# Sound.net
KiCad netlist of a schematic drawn in EAGLE
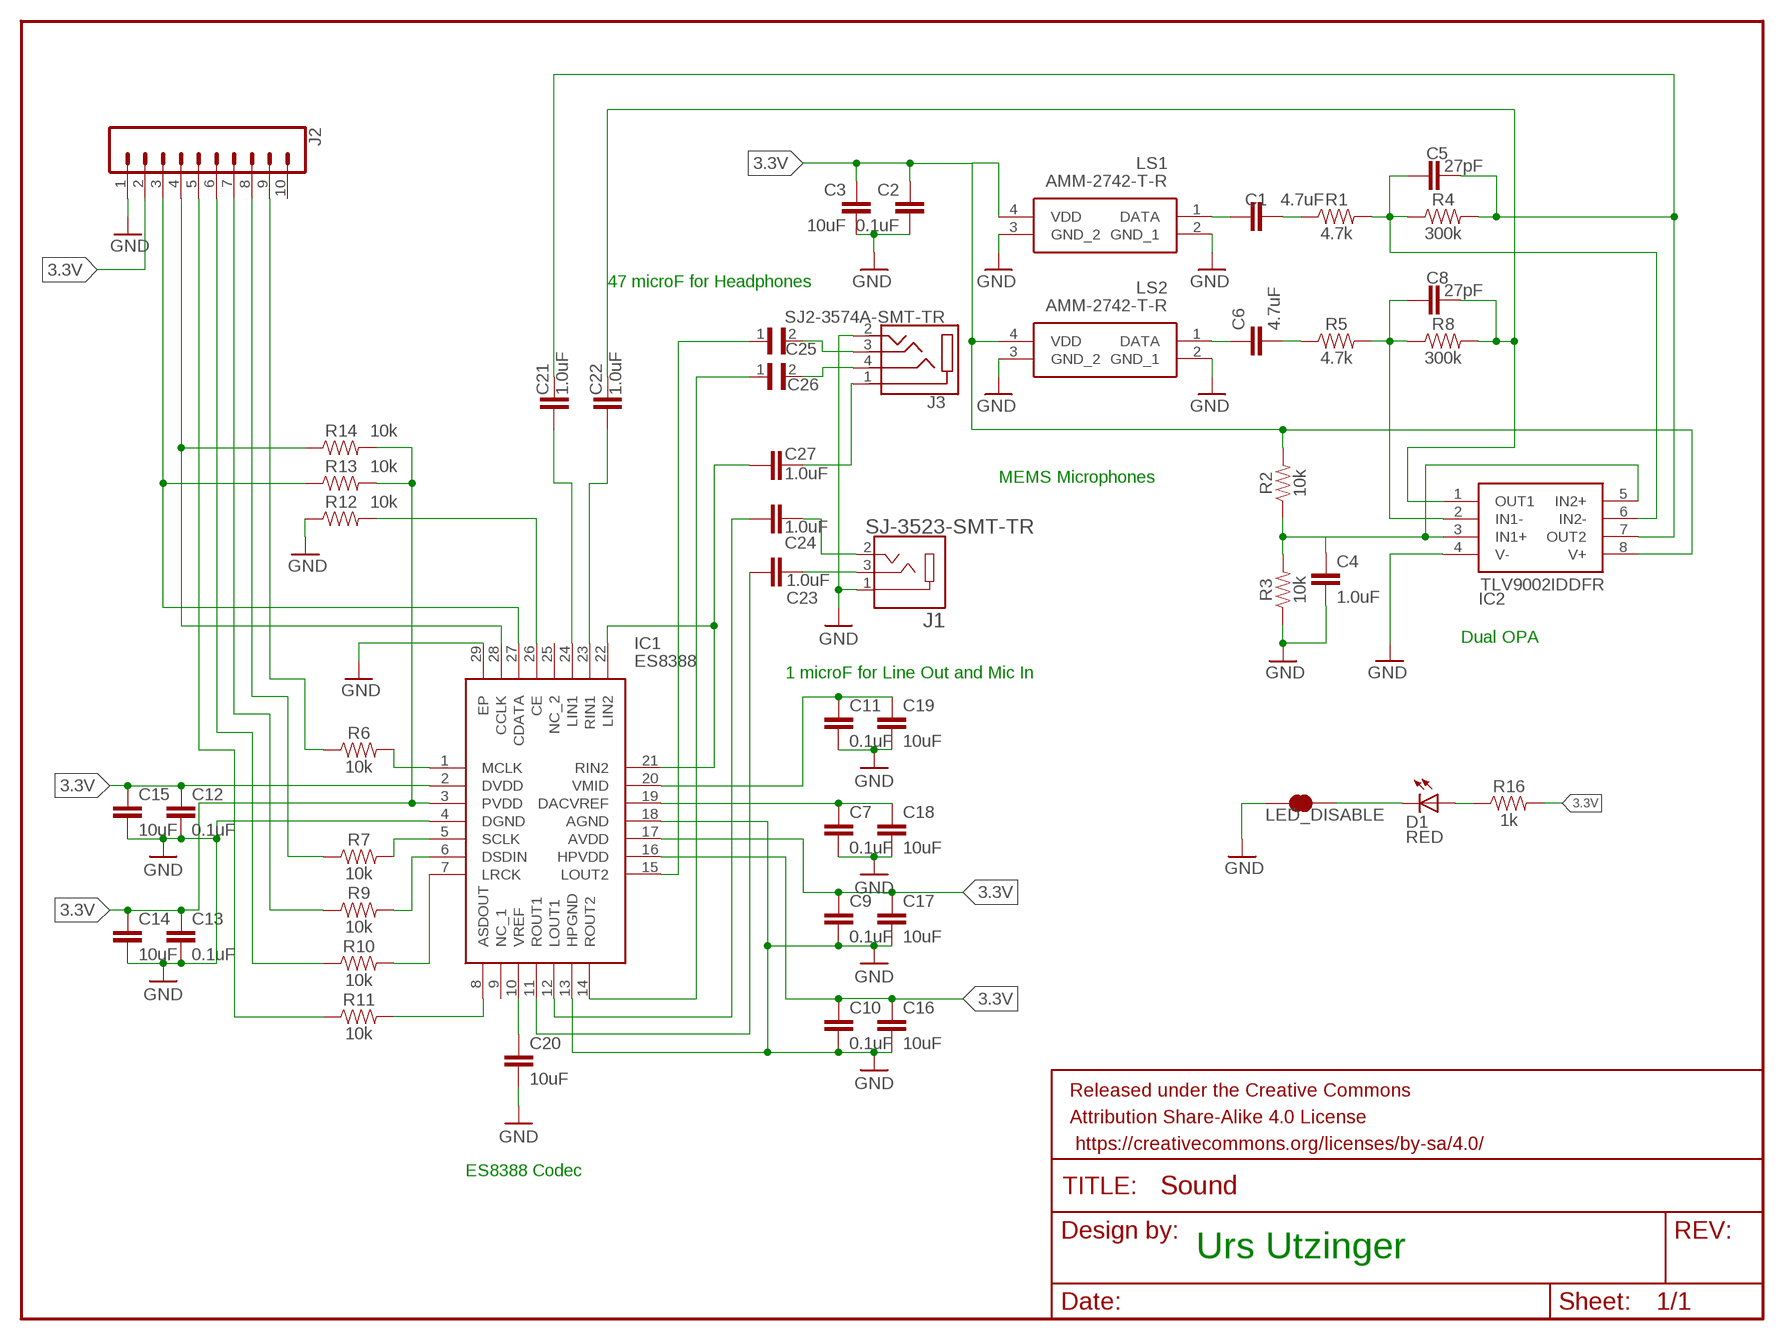
[diagram p0: schematic, sheet 1]

(export (version "E")
  (design (tool "Eeschema 10.0.6"))
  (components
    (comp (ref "C1")
      (value "4.7uF")
      (footprint "eagle-import:0603")
      (libsource (lib "eagle-import") (part "4.7UF0603"))
    )
    (comp (ref "C2")
      (value "0.1uF")
      (footprint "eagle-import:0603")
      (libsource (lib "eagle-import") (part "0.1UF-0603-25V-5%"))
    )
    (comp (ref "C3")
      (value "10uF")
      (footprint "eagle-import:0603")
      (libsource (lib "eagle-import") (part "10UF-0603-6.3V-20%"))
    )
    (comp (ref "C4")
      (value "1.0uF")
      (footprint "eagle-import:0603")
      (libsource (lib "eagle-import") (part "1.0UF-0603-16V-10%"))
    )
    (comp (ref "C5")
      (value "27pF")
      (footprint "eagle-import:0603")
      (libsource (lib "eagle-import") (part "27PF-0603-50V-5%"))
    )
    (comp (ref "C6")
      (value "4.7uF")
      (footprint "eagle-import:0603")
      (libsource (lib "eagle-import") (part "4.7UF0603"))
    )
    (comp (ref "C7")
      (value "0.1uF")
      (footprint "eagle-import:0603")
      (libsource (lib "eagle-import") (part "0.1UF-0603-25V-5%"))
    )
    (comp (ref "C8")
      (value "27pF")
      (footprint "eagle-import:0603")
      (libsource (lib "eagle-import") (part "27PF-0603-50V-5%"))
    )
    (comp (ref "C9")
      (value "0.1uF")
      (footprint "eagle-import:0603")
      (libsource (lib "eagle-import") (part "0.1UF-0603-25V-5%"))
    )
    (comp (ref "C10")
      (value "0.1uF")
      (footprint "eagle-import:0603")
      (libsource (lib "eagle-import") (part "0.1UF-0603-25V-5%"))
    )
    (comp (ref "C11")
      (value "0.1uF")
      (footprint "eagle-import:0603")
      (libsource (lib "eagle-import") (part "0.1UF-0603-25V-5%"))
    )
    (comp (ref "C12")
      (value "0.1uF")
      (footprint "eagle-import:0603")
      (libsource (lib "eagle-import") (part "0.1UF-0603-25V-5%"))
    )
    (comp (ref "C13")
      (value "0.1uF")
      (footprint "eagle-import:0603")
      (libsource (lib "eagle-import") (part "0.1UF-0603-25V-5%"))
    )
    (comp (ref "C14")
      (value "10uF")
      (footprint "eagle-import:0603")
      (libsource (lib "eagle-import") (part "10UF-0603-6.3V-20%"))
    )
    (comp (ref "C15")
      (value "10uF")
      (footprint "eagle-import:0603")
      (libsource (lib "eagle-import") (part "10UF-0603-6.3V-20%"))
    )
    (comp (ref "C16")
      (value "10uF")
      (footprint "eagle-import:0603")
      (libsource (lib "eagle-import") (part "10UF-0603-6.3V-20%"))
    )
    (comp (ref "C17")
      (value "10uF")
      (footprint "eagle-import:0603")
      (libsource (lib "eagle-import") (part "10UF-0603-6.3V-20%"))
    )
    (comp (ref "C18")
      (value "10uF")
      (footprint "eagle-import:0603")
      (libsource (lib "eagle-import") (part "10UF-0603-6.3V-20%"))
    )
    (comp (ref "C19")
      (value "10uF")
      (footprint "eagle-import:0603")
      (libsource (lib "eagle-import") (part "10UF-0603-6.3V-20%"))
    )
    (comp (ref "C20")
      (value "10uF")
      (footprint "eagle-import:0603")
      (libsource (lib "eagle-import") (part "10UF-0603-6.3V-20%"))
    )
    (comp (ref "C21")
      (value "1.0uF")
      (footprint "eagle-import:0603")
      (libsource (lib "eagle-import") (part "1.0UF-0603-16V-10%"))
    )
    (comp (ref "C22")
      (value "1.0uF")
      (footprint "eagle-import:0603")
      (libsource (lib "eagle-import") (part "1.0UF-0603-16V-10%"))
    )
    (comp (ref "C23")
      (value "1.0uF")
      (footprint "eagle-import:0603")
      (libsource (lib "eagle-import") (part "1.0UF-0603-16V-10%"))
    )
    (comp (ref "C24")
      (value "1.0uF")
      (footprint "eagle-import:0603")
      (libsource (lib "eagle-import") (part "1.0UF-0603-16V-10%"))
    )
    (comp (ref "C25")
      (value "GRM188R60J476ME15D")
      (footprint "eagle-import:CAPC1608X100N")
      (libsource (lib "eagle-import") (part "GRM188R60J476ME15D"))
    )
    (comp (ref "C26")
      (value "GRM188R60J476ME15D")
      (footprint "eagle-import:CAPC1608X100N")
      (libsource (lib "eagle-import") (part "GRM188R60J476ME15D"))
    )
    (comp (ref "C27")
      (value "1.0uF")
      (footprint "eagle-import:0603")
      (libsource (lib "eagle-import") (part "1.0UF-0603-16V-10%"))
    )
    (comp (ref "D1")
      (value "RED")
      (footprint "eagle-import:LED-0603")
      (libsource (lib "eagle-import") (part "LED-RED0603"))
    )
    (comp (ref "FRAME1")
      (value "FRAME-LETTERNO_PACKAGE")
      (footprint "eagle-import:DUMMY")
      (fields (field (name "DESIGNER") "Nobody"))
      (libsource (lib "eagle-import") (part "FRAME-LETTERNO_PACKAGE"))
    )
    (comp (ref "IC1")
      (value "ES8388")
      (footprint "eagle-import:QFN45P400X400X90-29N")
      (libsource (lib "eagle-import") (part "ES8388"))
    )
    (comp (ref "IC2")
      (value "TLV9002IDDFR")
      (footprint "eagle-import:SOT65P280X110-8N")
      (fields (field (name "MOUSER_PART_NUMBER") "595-TLV9002IDDFR"))
      (libsource (lib "eagle-import") (part "TLV9002IDDFR"))
    )
    (comp (ref "J1")
      (value "SJ-3523-SMT-TR")
      (footprint "eagle-import:CUI_SJ-3523-SMT-TR")
      (fields (field (name "MF") "CUI Inc"))
      (libsource (lib "eagle-import") (part "SJ-3523-SMT-TR"))
    )
    (comp (ref "J2")
      (value "CONN_10\"")
      (footprint "eagle-import:1X10")
      (libsource (lib "eagle-import") (part "CONN_10{dblquote}"))
    )
    (comp (ref "J3")
      (value "SJ2-3574A-SMT-TR")
      (footprint "eagle-import:CUI_SJ2-3574A-SMT-TR")
      (fields (field (name "MANUFACTURER") "CUI"))
      (libsource (lib "eagle-import") (part "SJ2-3574A-SMT-TR"))
    )
    (comp (ref "LED_DISABLE")
      (value "JUMPER-SMT_2_NC_TRACE_SILK")
      (footprint "eagle-import:SMT-JUMPER_2_NC_TRACE_SILK")
      (libsource (lib "eagle-import") (part "JUMPER-SMT_2_NC_TRACE_SILK"))
    )
    (comp (ref "LS1")
      (value "AMM-2742-T-R")
      (footprint "eagle-import:AMM2742TR")
      (fields (field (name "MOUSER_PART_NUMBER") "665-AMM-2742-T-R"))
      (libsource (lib "eagle-import") (part "AMM-2742-T-R"))
    )
    (comp (ref "LS2")
      (value "AMM-2742-T-R")
      (footprint "eagle-import:AMM2742TR")
      (fields (field (name "MOUSER_PART_NUMBER") "665-AMM-2742-T-R"))
      (libsource (lib "eagle-import") (part "AMM-2742-T-R"))
    )
    (comp (ref "R1")
      (value "4.7k")
      (footprint "eagle-import:0603")
      (libsource (lib "eagle-import") (part "4.7KOHM-0603-1/10W-1%"))
    )
    (comp (ref "R2")
      (value "10k")
      (footprint "eagle-import:0603")
      (libsource (lib "eagle-import") (part "10KOHM-0603-1/10W-1%"))
    )
    (comp (ref "R3")
      (value "10k")
      (footprint "eagle-import:0603")
      (libsource (lib "eagle-import") (part "10KOHM-0603-1/10W-1%"))
    )
    (comp (ref "R4")
      (value "300k")
      (footprint "eagle-import:0603")
      (libsource (lib "eagle-import") (part "300KOHM-0603-1/10W-1%"))
    )
    (comp (ref "R5")
      (value "4.7k")
      (footprint "eagle-import:0603")
      (libsource (lib "eagle-import") (part "4.7KOHM-0603-1/10W-1%"))
    )
    (comp (ref "R6")
      (value "10k")
      (footprint "eagle-import:0603")
      (libsource (lib "eagle-import") (part "10KOHM-0603-1/10W-1%"))
    )
    (comp (ref "R7")
      (value "10k")
      (footprint "eagle-import:0603")
      (libsource (lib "eagle-import") (part "10KOHM-0603-1/10W-1%"))
    )
    (comp (ref "R8")
      (value "300k")
      (footprint "eagle-import:0603")
      (libsource (lib "eagle-import") (part "300KOHM-0603-1/10W-1%"))
    )
    (comp (ref "R9")
      (value "10k")
      (footprint "eagle-import:0603")
      (libsource (lib "eagle-import") (part "10KOHM-0603-1/10W-1%"))
    )
    (comp (ref "R10")
      (value "10k")
      (footprint "eagle-import:0603")
      (libsource (lib "eagle-import") (part "10KOHM-0603-1/10W-1%"))
    )
    (comp (ref "R11")
      (value "10k")
      (footprint "eagle-import:0603")
      (libsource (lib "eagle-import") (part "10KOHM-0603-1/10W-1%"))
    )
    (comp (ref "R12")
      (value "10k")
      (footprint "eagle-import:0603")
      (libsource (lib "eagle-import") (part "10KOHM-0603-1/10W-1%"))
    )
    (comp (ref "R13")
      (value "10k")
      (footprint "eagle-import:0603")
      (libsource (lib "eagle-import") (part "10KOHM-0603-1/10W-1%"))
    )
    (comp (ref "R14")
      (value "10k")
      (footprint "eagle-import:0603")
      (libsource (lib "eagle-import") (part "10KOHM-0603-1/10W-1%"))
    )
    (comp (ref "R16")
      (value "1k")
      (footprint "eagle-import:0603")
      (libsource (lib "eagle-import") (part "1KOHM-0603-1/10W-1%"))
    )
  )
  (nets
    (net (code "1") (name "3.3V") (class "Default")
      (node (ref "C10") (pin "1") (pinfunction "1_1") (pintype "passive"))
      (node (ref "C12") (pin "1") (pinfunction "1_1") (pintype "passive"))
      (node (ref "C13") (pin "1") (pinfunction "1_1") (pintype "passive"))
      (node (ref "C14") (pin "1") (pinfunction "1_1") (pintype "passive"))
      (node (ref "C15") (pin "1") (pinfunction "1_1") (pintype "passive"))
      (node (ref "C16") (pin "1") (pinfunction "1_1") (pintype "passive"))
      (node (ref "C17") (pin "1") (pinfunction "1_1") (pintype "passive"))
      (node (ref "C2") (pin "1") (pinfunction "1_1") (pintype "passive"))
      (node (ref "C3") (pin "1") (pinfunction "1_1") (pintype "passive"))
      (node (ref "C9") (pin "1") (pinfunction "1_1") (pintype "passive"))
      (node (ref "IC1") (pin "16") (pinfunction "HPVDD_16") (pintype "bidirectional"))
      (node (ref "IC1") (pin "17") (pinfunction "AVDD_17") (pintype "bidirectional"))
      (node (ref "IC1") (pin "2") (pinfunction "DVDD_2") (pintype "bidirectional"))
      (node (ref "IC1") (pin "3") (pinfunction "PVDD_3") (pintype "bidirectional"))
      (node (ref "IC2") (pin "8") (pinfunction "V+_8") (pintype "bidirectional"))
      (node (ref "J2") (pin "2") (pinfunction "2_2") (pintype "passive"))
      (node (ref "LS1") (pin "4") (pinfunction "VDD_4") (pintype "bidirectional"))
      (node (ref "LS2") (pin "4") (pinfunction "VDD_4") (pintype "bidirectional"))
      (node (ref "R13") (pin "2") (pinfunction "2_2") (pintype "passive"))
      (node (ref "R14") (pin "2") (pinfunction "2_2") (pintype "passive"))
      (node (ref "R16") (pin "2") (pinfunction "2_2") (pintype "passive"))
      (node (ref "R2") (pin "2") (pinfunction "2_2") (pintype "passive"))
    )
    (net (code "2") (name "GND") (class "Default")
      (node (ref "C10") (pin "2") (pinfunction "2_2") (pintype "passive"))
      (node (ref "C11") (pin "2") (pinfunction "2_2") (pintype "passive"))
      (node (ref "C12") (pin "2") (pinfunction "2_2") (pintype "passive"))
      (node (ref "C13") (pin "2") (pinfunction "2_2") (pintype "passive"))
      (node (ref "C14") (pin "2") (pinfunction "2_2") (pintype "passive"))
      (node (ref "C15") (pin "2") (pinfunction "2_2") (pintype "passive"))
      (node (ref "C16") (pin "2") (pinfunction "2_2") (pintype "passive"))
      (node (ref "C17") (pin "2") (pinfunction "2_2") (pintype "passive"))
      (node (ref "C18") (pin "2") (pinfunction "2_2") (pintype "passive"))
      (node (ref "C19") (pin "2") (pinfunction "2_2") (pintype "passive"))
      (node (ref "C2") (pin "2") (pinfunction "2_2") (pintype "passive"))
      (node (ref "C20") (pin "2") (pinfunction "2_2") (pintype "passive"))
      (node (ref "C3") (pin "2") (pinfunction "2_2") (pintype "passive"))
      (node (ref "C4") (pin "2") (pinfunction "2_2") (pintype "passive"))
      (node (ref "C7") (pin "2") (pinfunction "2_2") (pintype "passive"))
      (node (ref "C9") (pin "2") (pinfunction "2_2") (pintype "passive"))
      (node (ref "IC1") (pin "13") (pinfunction "HPGND_13") (pintype "bidirectional"))
      (node (ref "IC1") (pin "18") (pinfunction "AGND_18") (pintype "bidirectional"))
      (node (ref "IC1") (pin "29") (pinfunction "EP_29") (pintype "bidirectional"))
      (node (ref "IC1") (pin "4") (pinfunction "DGND_4") (pintype "bidirectional"))
      (node (ref "IC2") (pin "4") (pinfunction "V-_4") (pintype "bidirectional"))
      (node (ref "J1") (pin "1") (pinfunction "1_1") (pintype "passive"))
      (node (ref "J2") (pin "1") (pinfunction "1_1") (pintype "passive"))
      (node (ref "J3") (pin "2") (pinfunction "2_2") (pintype "passive"))
      (node (ref "LED_DISABLE") (pin "1") (pinfunction "1_1") (pintype "passive"))
      (node (ref "LS1") (pin "2") (pinfunction "GND_1_2") (pintype "bidirectional"))
      (node (ref "LS1") (pin "3") (pinfunction "GND_2_3") (pintype "bidirectional"))
      (node (ref "LS2") (pin "2") (pinfunction "GND_1_2") (pintype "bidirectional"))
      (node (ref "LS2") (pin "3") (pinfunction "GND_2_3") (pintype "bidirectional"))
      (node (ref "R12") (pin "1") (pinfunction "1_1") (pintype "passive"))
      (node (ref "R3") (pin "1") (pinfunction "1_1") (pintype "passive"))
    )
    (net (code "3") (name "Net-(C1-Pad2)") (class "Default")
      (node (ref "C1") (pin "2") (pinfunction "2_2") (pintype "passive"))
      (node (ref "R1") (pin "1") (pinfunction "1_1") (pintype "passive"))
    )
    (net (code "4") (name "Net-(C6-Pad2)") (class "Default")
      (node (ref "C6") (pin "2") (pinfunction "2_2") (pintype "passive"))
      (node (ref "R5") (pin "1") (pinfunction "1_1") (pintype "passive"))
    )
    (net (code "5") (name "Net-(C23-Pad1)") (class "Default")
      (node (ref "C23") (pin "1") (pinfunction "1_1") (pintype "passive"))
      (node (ref "J1") (pin "3") (pinfunction "3_3") (pintype "passive"))
    )
    (net (code "6") (name "Net-(C24-Pad1)") (class "Default")
      (node (ref "C24") (pin "1") (pinfunction "1_1") (pintype "passive"))
      (node (ref "J1") (pin "2") (pinfunction "2_2") (pintype "passive"))
    )
    (net (code "7") (name "Net-(C25-Pad2)") (class "Default")
      (node (ref "C25") (pin "2") (pinfunction "2_2") (pintype "passive"))
      (node (ref "J3") (pin "3") (pinfunction "3_3") (pintype "passive"))
    )
    (net (code "8") (name "Net-(C26-Pad2)") (class "Default")
      (node (ref "C26") (pin "2") (pinfunction "2_2") (pintype "passive"))
      (node (ref "J3") (pin "4") (pinfunction "4_4") (pintype "passive"))
    )
    (net (code "9") (name "Net-(C27-Pad2)") (class "Default")
      (node (ref "C27") (pin "2") (pinfunction "2_2") (pintype "passive"))
      (node (ref "J3") (pin "1") (pinfunction "1_1") (pintype "passive"))
    )
    (net (code "10") (name "Net-(D1-PadA)") (class "Default")
      (node (ref "D1") (pin "A") (pinfunction "A_A") (pintype "passive"))
      (node (ref "R16") (pin "1") (pinfunction "1_1") (pintype "passive"))
    )
    (net (code "11") (name "Net-(D1-PadC)") (class "Default")
      (node (ref "D1") (pin "C") (pinfunction "C_C") (pintype "passive"))
      (node (ref "LED_DISABLE") (pin "2") (pinfunction "2_2") (pintype "passive"))
    )
    (net (code "12") (name "Net-(IC1-ASDOUT)") (class "Default")
      (node (ref "IC1") (pin "8") (pinfunction "ASDOUT_8") (pintype "bidirectional"))
      (node (ref "R11") (pin "2") (pinfunction "2_2") (pintype "passive"))
    )
    (net (code "13") (name "Net-(IC1-CCLK)") (class "Default")
      (node (ref "IC1") (pin "28") (pinfunction "CCLK_28") (pintype "bidirectional"))
      (node (ref "J2") (pin "4") (pinfunction "4_4") (pintype "passive"))
      (node (ref "R14") (pin "1") (pinfunction "1_1") (pintype "passive"))
    )
    (net (code "14") (name "Net-(IC1-CDATA)") (class "Default")
      (node (ref "IC1") (pin "27") (pinfunction "CDATA_27") (pintype "bidirectional"))
      (node (ref "J2") (pin "3") (pinfunction "3_3") (pintype "passive"))
      (node (ref "R13") (pin "1") (pinfunction "1_1") (pintype "passive"))
    )
    (net (code "15") (name "Net-(IC1-CE)") (class "Default")
      (node (ref "IC1") (pin "26") (pinfunction "CE_26") (pintype "bidirectional"))
      (node (ref "R12") (pin "2") (pinfunction "2_2") (pintype "passive"))
    )
    (net (code "16") (name "Net-(IC1-DACVREF)") (class "Default")
      (node (ref "C18") (pin "1") (pinfunction "1_1") (pintype "passive"))
      (node (ref "C7") (pin "1") (pinfunction "1_1") (pintype "passive"))
      (node (ref "IC1") (pin "19") (pinfunction "DACVREF_19") (pintype "bidirectional"))
    )
    (net (code "17") (name "Net-(IC1-DSDIN)") (class "Default")
      (node (ref "IC1") (pin "6") (pinfunction "DSDIN_6") (pintype "bidirectional"))
      (node (ref "R9") (pin "2") (pinfunction "2_2") (pintype "passive"))
    )
    (net (code "18") (name "Net-(IC1-LIN1)") (class "Default")
      (node (ref "C21") (pin "1") (pinfunction "1_1") (pintype "passive"))
      (node (ref "IC1") (pin "24") (pinfunction "LIN1_24") (pintype "bidirectional"))
    )
    (net (code "19") (name "Net-(IC1-LIN2)") (class "Default")
      (node (ref "C27") (pin "1") (pinfunction "1_1") (pintype "passive"))
      (node (ref "IC1") (pin "21") (pinfunction "RIN2_21") (pintype "bidirectional"))
      (node (ref "IC1") (pin "22") (pinfunction "LIN2_22") (pintype "bidirectional"))
    )
    (net (code "20") (name "Net-(IC1-LOUT1)") (class "Default")
      (node (ref "C24") (pin "2") (pinfunction "2_2") (pintype "passive"))
      (node (ref "IC1") (pin "12") (pinfunction "LOUT1_12") (pintype "bidirectional"))
    )
    (net (code "21") (name "Net-(IC1-LOUT2)") (class "Default")
      (node (ref "C25") (pin "1") (pinfunction "1_1") (pintype "passive"))
      (node (ref "IC1") (pin "15") (pinfunction "LOUT2_15") (pintype "bidirectional"))
    )
    (net (code "22") (name "Net-(IC1-LRCK)") (class "Default")
      (node (ref "IC1") (pin "7") (pinfunction "LRCK_7") (pintype "bidirectional"))
      (node (ref "R10") (pin "2") (pinfunction "2_2") (pintype "passive"))
    )
    (net (code "23") (name "Net-(IC1-MCLK)") (class "Default")
      (node (ref "IC1") (pin "1") (pinfunction "MCLK_1") (pintype "bidirectional"))
      (node (ref "R6") (pin "2") (pinfunction "2_2") (pintype "passive"))
    )
    (net (code "24") (name "Net-(IC1-RIN1)") (class "Default")
      (node (ref "C22") (pin "1") (pinfunction "1_1") (pintype "passive"))
      (node (ref "IC1") (pin "23") (pinfunction "RIN1_23") (pintype "bidirectional"))
    )
    (net (code "25") (name "Net-(IC1-ROUT1)") (class "Default")
      (node (ref "C23") (pin "2") (pinfunction "2_2") (pintype "passive"))
      (node (ref "IC1") (pin "11") (pinfunction "ROUT1_11") (pintype "bidirectional"))
    )
    (net (code "26") (name "Net-(IC1-ROUT2)") (class "Default")
      (node (ref "C26") (pin "1") (pinfunction "1_1") (pintype "passive"))
      (node (ref "IC1") (pin "14") (pinfunction "ROUT2_14") (pintype "bidirectional"))
    )
    (net (code "27") (name "Net-(IC1-SCLK)") (class "Default")
      (node (ref "IC1") (pin "5") (pinfunction "SCLK_5") (pintype "bidirectional"))
      (node (ref "R7") (pin "2") (pinfunction "2_2") (pintype "passive"))
    )
    (net (code "28") (name "Net-(IC1-VMID)") (class "Default")
      (node (ref "C11") (pin "1") (pinfunction "1_1") (pintype "passive"))
      (node (ref "C19") (pin "1") (pinfunction "1_1") (pintype "passive"))
      (node (ref "IC1") (pin "20") (pinfunction "VMID_20") (pintype "bidirectional"))
    )
    (net (code "29") (name "Net-(IC1-VREF)") (class "Default")
      (node (ref "C20") (pin "1") (pinfunction "1_1") (pintype "passive"))
      (node (ref "IC1") (pin "10") (pinfunction "VREF_10") (pintype "bidirectional"))
    )
    (net (code "30") (name "Net-(IC2-IN1+)") (class "Default")
      (node (ref "C4") (pin "1") (pinfunction "1_1") (pintype "passive"))
      (node (ref "IC2") (pin "3") (pinfunction "IN1+_3") (pintype "bidirectional"))
      (node (ref "IC2") (pin "5") (pinfunction "IN2+_5") (pintype "bidirectional"))
      (node (ref "R2") (pin "1") (pinfunction "1_1") (pintype "passive"))
      (node (ref "R3") (pin "2") (pinfunction "2_2") (pintype "passive"))
    )
    (net (code "31") (name "Net-(IC2-IN1-)") (class "Default")
      (node (ref "C8") (pin "1") (pinfunction "1_1") (pintype "passive"))
      (node (ref "IC2") (pin "2") (pinfunction "IN1-_2") (pintype "bidirectional"))
      (node (ref "R5") (pin "2") (pinfunction "2_2") (pintype "passive"))
      (node (ref "R8") (pin "1") (pinfunction "1_1") (pintype "passive"))
    )
    (net (code "32") (name "Net-(IC2-IN2-)") (class "Default")
      (node (ref "C5") (pin "1") (pinfunction "1_1") (pintype "passive"))
      (node (ref "IC2") (pin "6") (pinfunction "IN2-_6") (pintype "bidirectional"))
      (node (ref "R1") (pin "2") (pinfunction "2_2") (pintype "passive"))
      (node (ref "R4") (pin "1") (pinfunction "1_1") (pintype "passive"))
    )
    (net (code "33") (name "Net-(IC2-OUT1)") (class "Default")
      (node (ref "C22") (pin "2") (pinfunction "2_2") (pintype "passive"))
      (node (ref "C8") (pin "2") (pinfunction "2_2") (pintype "passive"))
      (node (ref "IC2") (pin "1") (pinfunction "OUT1_1") (pintype "bidirectional"))
      (node (ref "R8") (pin "2") (pinfunction "2_2") (pintype "passive"))
    )
    (net (code "34") (name "Net-(IC2-OUT2)") (class "Default")
      (node (ref "C21") (pin "2") (pinfunction "2_2") (pintype "passive"))
      (node (ref "C5") (pin "2") (pinfunction "2_2") (pintype "passive"))
      (node (ref "IC2") (pin "7") (pinfunction "OUT2_7") (pintype "bidirectional"))
      (node (ref "R4") (pin "2") (pinfunction "2_2") (pintype "passive"))
    )
    (net (code "35") (name "Net-(J2-Pad5)") (class "Default")
      (node (ref "J2") (pin "5") (pinfunction "5_5") (pintype "passive"))
      (node (ref "R11") (pin "1") (pinfunction "1_1") (pintype "passive"))
    )
    (net (code "36") (name "Net-(J2-Pad6)") (class "Default")
      (node (ref "J2") (pin "6") (pinfunction "6_6") (pintype "passive"))
      (node (ref "R10") (pin "1") (pinfunction "1_1") (pintype "passive"))
    )
    (net (code "37") (name "Net-(J2-Pad7)") (class "Default")
      (node (ref "J2") (pin "7") (pinfunction "7_7") (pintype "passive"))
      (node (ref "R9") (pin "1") (pinfunction "1_1") (pintype "passive"))
    )
    (net (code "38") (name "Net-(J2-Pad8)") (class "Default")
      (node (ref "J2") (pin "8") (pinfunction "8_8") (pintype "passive"))
      (node (ref "R7") (pin "1") (pinfunction "1_1") (pintype "passive"))
    )
    (net (code "39") (name "Net-(J2-Pad9)") (class "Default")
      (node (ref "J2") (pin "9") (pinfunction "9_9") (pintype "passive"))
      (node (ref "R6") (pin "1") (pinfunction "1_1") (pintype "passive"))
    )
    (net (code "40") (name "Net-(LS1-DATA)") (class "Default")
      (node (ref "C1") (pin "1") (pinfunction "1_1") (pintype "passive"))
      (node (ref "LS1") (pin "1") (pinfunction "DATA_1") (pintype "bidirectional"))
    )
    (net (code "41") (name "Net-(LS2-DATA)") (class "Default")
      (node (ref "C6") (pin "1") (pinfunction "1_1") (pintype "passive"))
      (node (ref "LS2") (pin "1") (pinfunction "DATA_1") (pintype "bidirectional"))
    )
    (net (code "42") (name "unconnected-(IC1-NC_1-Pad9)") (class "Default")
      (node (ref "IC1") (pin "9") (pinfunction "NC_1_9") (pintype "bidirectional"))
    )
    (net (code "43") (name "unconnected-(IC1-NC_2-Pad25)") (class "Default")
      (node (ref "IC1") (pin "25") (pinfunction "NC_2_25") (pintype "bidirectional"))
    )
    (net (code "44") (name "unconnected-(J2-Pad10)") (class "Default")
      (node (ref "J2") (pin "10") (pinfunction "10_10") (pintype "passive"))
    )
  )
)
